# Sound_v2_SCH.net
KiCad netlist of a schematic drawn in Altium Designer
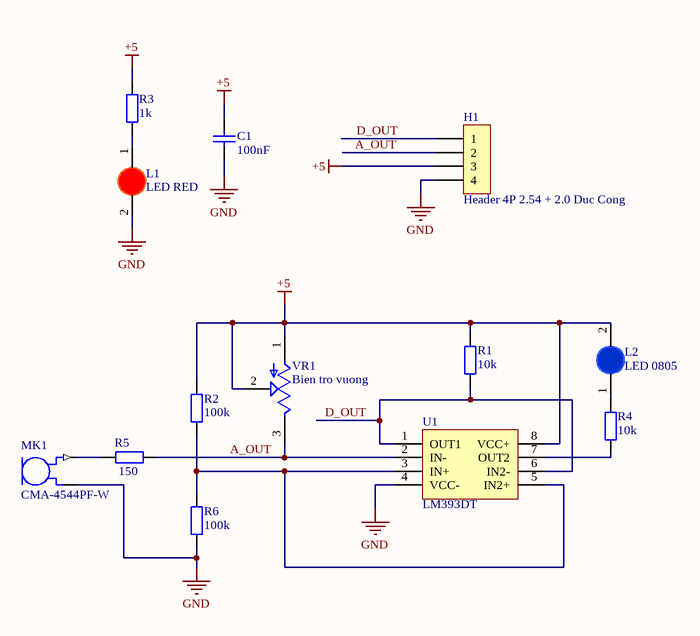
[diagram p0: Sound_v2_SCH.SchDoc]

(export (version "E")
  (design (tool "Eeschema 10.0.6"))
  (components
    (comp (ref "C1")
      (value "100nF")
      (footprint "tu 0603")
      (description "Dán")
      (libsource (lib "namnt_Lib") (part "Tu 0603 104 50V 10%"))
    )
    (comp (ref "H1")
      (value "Header 4P 2.54 + 2.0 Duc Cong")
      (footprint "Header 4P DC 2.54 + 2.0")
      (description "Cắm")
      (libsource (lib "namnt_Lib") (part "Header 4P 2.54 + 2.0 Duc Cong"))
    )
    (comp (ref "L1")
      (value "LED RED")
      (footprint "LED-0805-Red")
      (description "Dán")
      (libsource (lib "namnt_Lib") (part "LED 0805 Do"))
    )
    (comp (ref "L2")
      (value "LED 0805")
      (footprint "LED-0805-Blue")
      (description "Dán")
      (libsource (lib "namnt_Lib") (part "LED 0805 Xanh Duong"))
    )
    (comp (ref "MK1")
      (value "CMA-4544PF-W")
      (footprint "MIC_CMA-4544PF-W")
      (description "9.7 mm, Omnidirectional, PCB Mount, 3.0 Vdc, Electret Condenser Microphone")
      (fields (field (name "MF") "Same Sky"))
      (libsource (lib "namnt_Lib") (part "CMA-4544PF-W"))
    )
    (comp (ref "R1")
      (value "10k")
      (footprint "tro smd 0603")
      (description "Dán")
      (libsource (lib "namnt_Lib") (part "Tro 0603 5% 100k"))
    )
    (comp (ref "R2")
      (value "100k")
      (footprint "tro smd 0603")
      (description "Dán")
      (libsource (lib "namnt_Lib") (part "Tro 0603 5% 100k"))
    )
    (comp (ref "R3")
      (value "1k")
      (footprint "tro smd 0603")
      (description "Dán")
      (libsource (lib "namnt_Lib") (part "Tro 0603 1% 1k"))
    )
    (comp (ref "R4")
      (value "10k")
      (footprint "tro smd 0603")
      (description "Dán")
      (libsource (lib "namnt_Lib") (part "Tro 0603 5% 100k"))
    )
    (comp (ref "R5")
      (value "150")
      (footprint "tro smd 0603")
      (description "Dán")
      (libsource (lib "namnt_Lib") (part "Tro 0603 5% 150R"))
    )
    (comp (ref "R6")
      (value "100k")
      (footprint "tro smd 0603")
      (description "Dán")
      (libsource (lib "namnt_Lib") (part "Tro 0603 5% 100k"))
    )
    (comp (ref "U1")
      (value "LM393DT")
      (footprint "SOIC8_50_328_25X90_SMT")
      (description "Comparator General Purpose CMOS, DTL, ECL, MOS, Open-Collector, TTL 8-SO")
      (fields (field (name "MANUFACTURER") "Texas Instruments"))
      (libsource (lib "namnt_Lib") (part "IC_LM393DT"))
    )
    (comp (ref "VR1")
      (value "Bien tro vuong")
      (footprint "TRIM_3362P-1-102")
      (description "TRIMMER - 1/4in SQ ST CERMET ¦ Bourns 3362P-1-102")
      (fields (field (name "MF") "Bourns") (field (name "MP") "3362P-1-102"))
      (libsource (lib "namnt_Lib") (part "Bien tro vuong"))
    )
  )
  (nets
    (net (code "1") (name "+5") (class "Default")
      (node (ref "C1") (pin "1") (pinfunction "1_1") (pintype "passive"))
      (node (ref "H1") (pin "3") (pinfunction "3_3") (pintype "passive"))
      (node (ref "L2") (pin "2") (pinfunction "K_2") (pintype "passive"))
      (node (ref "R1") (pin "2") (pinfunction "2_2") (pintype "passive"))
      (node (ref "R2") (pin "2") (pinfunction "2_2") (pintype "passive"))
      (node (ref "R3") (pin "2") (pinfunction "2_2") (pintype "passive"))
      (node (ref "U1") (pin "8") (pinfunction "VCC+_8") (pintype "passive"))
      (node (ref "VR1") (pin "1") (pinfunction "CCW_1") (pintype "passive"))
      (node (ref "VR1") (pin "2") (pinfunction "WIPER_2") (pintype "passive"))
    )
    (net (code "2") (name "/A_OUT") (class "Default")
      (node (ref "H1") (pin "2") (pinfunction "2_2") (pintype "passive"))
      (node (ref "R5") (pin "2") (pinfunction "2_2") (pintype "passive"))
      (node (ref "U1") (pin "2") (pinfunction "IN-_2") (pintype "passive"))
      (node (ref "VR1") (pin "3") (pinfunction "CW_3") (pintype "passive"))
    )
    (net (code "3") (name "/D_OUT") (class "Default")
      (node (ref "H1") (pin "1") (pinfunction "1_1") (pintype "passive"))
      (node (ref "R1") (pin "1") (pinfunction "1_1") (pintype "passive"))
      (node (ref "U1") (pin "1") (pinfunction "OUT1_1") (pintype "passive"))
      (node (ref "U1") (pin "6") (pinfunction "IN2-_6") (pintype "passive"))
    )
    (net (code "4") (name "GND") (class "Default")
      (node (ref "C1") (pin "2") (pinfunction "2_2") (pintype "passive"))
      (node (ref "H1") (pin "4") (pinfunction "4_4") (pintype "passive"))
      (node (ref "L1") (pin "2") (pinfunction "K_2") (pintype "passive"))
      (node (ref "MK1") (pin "2") (pinfunction "GND_2") (pintype "power_in"))
      (node (ref "R6") (pin "1") (pinfunction "1_1") (pintype "passive"))
      (node (ref "U1") (pin "4") (pinfunction "VCC-_4") (pintype "passive"))
    )
    (net (code "5") (name "Net-(L1-A)") (class "Default")
      (node (ref "L1") (pin "1") (pinfunction "A_1") (pintype "passive"))
      (node (ref "R3") (pin "1") (pinfunction "1_1") (pintype "passive"))
    )
    (net (code "6") (name "Net-(L2-A)") (class "Default")
      (node (ref "L2") (pin "1") (pinfunction "A_1") (pintype "passive"))
      (node (ref "R4") (pin "2") (pinfunction "2_2") (pintype "passive"))
    )
    (net (code "7") (name "Net-(MK1-OUT)") (class "Default")
      (node (ref "MK1") (pin "1") (pinfunction "OUT_1") (pintype "output"))
      (node (ref "R5") (pin "1") (pinfunction "1_1") (pintype "passive"))
    )
    (net (code "8") (name "Net-(U1-IN+)") (class "Default")
      (node (ref "R2") (pin "1") (pinfunction "1_1") (pintype "passive"))
      (node (ref "R6") (pin "2") (pinfunction "2_2") (pintype "passive"))
      (node (ref "U1") (pin "3") (pinfunction "IN+_3") (pintype "passive"))
      (node (ref "U1") (pin "5") (pinfunction "IN2+_5") (pintype "passive"))
    )
    (net (code "9") (name "Net-(U1-OUT2)") (class "Default")
      (node (ref "R4") (pin "1") (pinfunction "1_1") (pintype "passive"))
      (node (ref "U1") (pin "7") (pinfunction "OUT2_7") (pintype "passive"))
    )
  )
)
